# Audio.net
KiCad netlist of a schematic drawn in Altium Designer
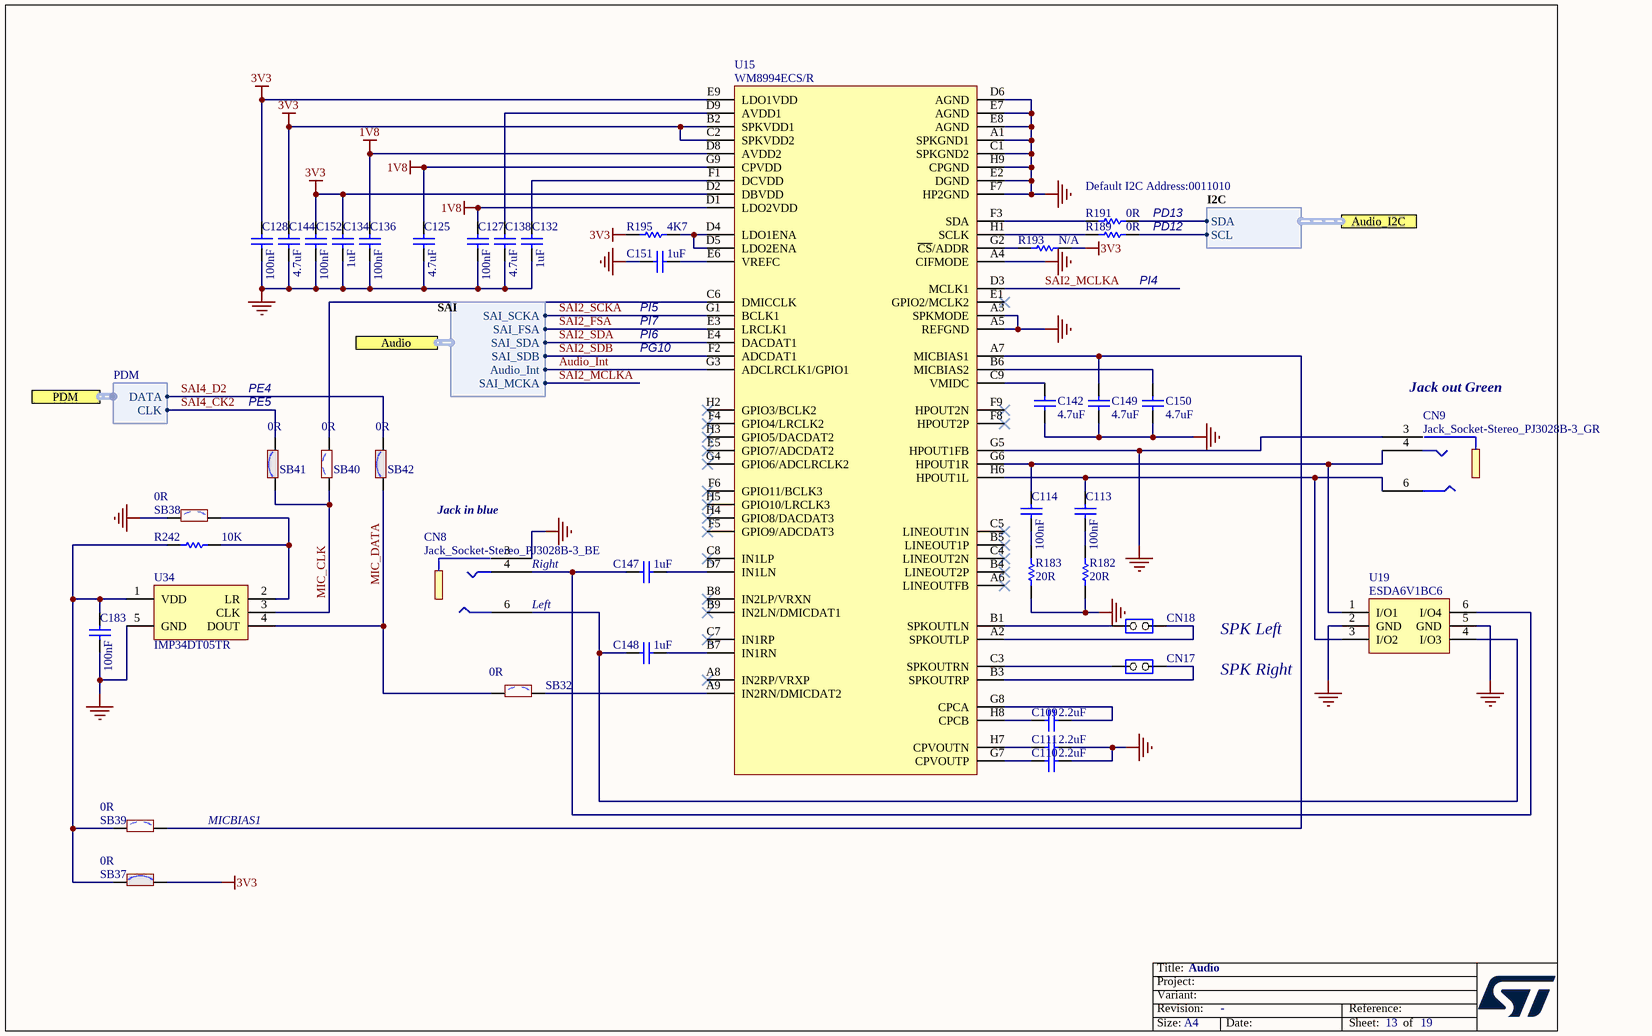
[diagram p0: Audio.SchDoc]

(export (version "E")
  (design (tool "Eeschema 10.0.6"))
  (components
    (comp (ref "C109")
      (value "2.2uF")
      (footprint "C0603")
      (description "Capacitor, MLCC, 2.2uF, 10V, X5R, 10%, 0603, T=0,8mm")
      (fields
        (field (name "INTERNAL_PART_NUMBER") "MCD-00012")
        (field (name "MANUFACTURER_PART_NUMBER") "CC0603KRX5R6BB225")
        (field (name "PROVIDED_BY") "Subcon")
      )
      (libsource (lib "MCD_PARTS_database") (part "Capacitor"))
    )
    (comp (ref "C110")
      (value "2.2uF")
      (footprint "C0603")
      (description "Capacitor, MLCC, 2.2uF, 10V, X5R, 10%, 0603, T=0,8mm")
      (fields
        (field (name "INTERNAL_PART_NUMBER") "MCD-00012")
        (field (name "MANUFACTURER_PART_NUMBER") "CC0603KRX5R6BB225")
        (field (name "PROVIDED_BY") "Subcon")
      )
      (libsource (lib "MCD_PARTS_database") (part "Capacitor"))
    )
    (comp (ref "C111")
      (value "2.2uF")
      (footprint "C0603")
      (description "Capacitor, MLCC, 2.2uF, 10V, X5R, 10%, 0603, T=0,8mm")
      (fields
        (field (name "INTERNAL_PART_NUMBER") "MCD-00012")
        (field (name "MANUFACTURER_PART_NUMBER") "CC0603KRX5R6BB225")
        (field (name "PROVIDED_BY") "Subcon")
      )
      (libsource (lib "MCD_PARTS_database") (part "Capacitor"))
    )
    (comp (ref "C113")
      (value "100nF")
      (footprint "C0402")
      (description "Capacitor, MLCC, 100nF, 16V, X7R, +/-10%, 0402, T=0.5mm")
      (fields
        (field (name "INTERNAL_PART_NUMBER") "MCD-00006")
        (field (name "MANUFACTURER_PART_NUMBER") "CC0402KRX7R7BB104")
      )
      (libsource (lib "MCD_PARTS_database") (part "Capacitor"))
    )
    (comp (ref "C114")
      (value "100nF")
      (footprint "C0402")
      (description "Capacitor, MLCC, 100nF, 16V, X7R, +/-10%, 0402, T=0.5mm")
      (fields
        (field (name "INTERNAL_PART_NUMBER") "MCD-00006")
        (field (name "MANUFACTURER_PART_NUMBER") "CC0402KRX7R7BB104")
      )
      (libsource (lib "MCD_PARTS_database") (part "Capacitor"))
    )
    (comp (ref "C125")
      (value "4.7uF")
      (footprint "C0603")
      (description "Capacitor, MLCC, 4.7uF, 16V, X5R, 10%, 0603, T=0.8mm")
      (fields
        (field (name "INTERNAL_PART_NUMBER") "MCD-00009")
        (field (name "MANUFACTURER_PART_NUMBER") "CC0603KRX5R7BB475")
        (field (name "PROVIDED_BY") "subcon")
      )
      (libsource (lib "MCD_PARTS_database") (part "Capacitor"))
    )
    (comp (ref "C127")
      (value "100nF")
      (footprint "C0402")
      (description "Capacitor, MLCC, 100nF, 16V, X7R, +/-10%, 0402, T=0.5mm")
      (fields
        (field (name "INTERNAL_PART_NUMBER") "MCD-00006")
        (field (name "MANUFACTURER_PART_NUMBER") "CC0402KRX7R7BB104")
      )
      (libsource (lib "MCD_PARTS_database") (part "Capacitor"))
    )
    (comp (ref "C128")
      (value "100nF")
      (footprint "C0402")
      (description "Capacitor, MLCC, 100nF, 16V, X7R, +/-10%, 0402, T=0.5mm")
      (fields
        (field (name "INTERNAL_PART_NUMBER") "MCD-00006")
        (field (name "MANUFACTURER_PART_NUMBER") "CC0402KRX7R7BB104")
      )
      (libsource (lib "MCD_PARTS_database") (part "Capacitor"))
    )
    (comp (ref "C132")
      (value "1uF")
      (footprint "C0603")
      (description "Capacitor, MLCC, 1uF, 16V, X5R, 10%, 0603, T=0,8mm")
      (fields
        (field (name "INTERNAL_PART_NUMBER") "MCD-00010")
        (field (name "MANUFACTURER_PART_NUMBER") "CC0603KRX5R7BB105")
        (field (name "PROVIDED_BY") "Subcon")
      )
      (libsource (lib "MCD_PARTS_database") (part "Capacitor"))
    )
    (comp (ref "C134")
      (value "1uF")
      (footprint "C0603")
      (description "Capacitor, MLCC, 1uF, 16V, X5R, 10%, 0603, T=0,8mm")
      (fields
        (field (name "INTERNAL_PART_NUMBER") "MCD-00010")
        (field (name "MANUFACTURER_PART_NUMBER") "CC0603KRX5R7BB105")
        (field (name "PROVIDED_BY") "Subcon")
      )
      (libsource (lib "MCD_PARTS_database") (part "Capacitor"))
    )
    (comp (ref "C136")
      (value "100nF")
      (footprint "C0402")
      (description "Capacitor, MLCC, 100nF, 16V, X7R, +/-10%, 0402, T=0.5mm")
      (fields
        (field (name "INTERNAL_PART_NUMBER") "MCD-00006")
        (field (name "MANUFACTURER_PART_NUMBER") "CC0402KRX7R7BB104")
      )
      (libsource (lib "MCD_PARTS_database") (part "Capacitor"))
    )
    (comp (ref "C138")
      (value "4.7uF")
      (footprint "C0603")
      (description "Capacitor, MLCC, 4.7uF, 16V, X5R, 10%, 0603, T=0.8mm")
      (fields
        (field (name "INTERNAL_PART_NUMBER") "MCD-00009")
        (field (name "MANUFACTURER_PART_NUMBER") "CC0603KRX5R7BB475")
        (field (name "PROVIDED_BY") "subcon")
      )
      (libsource (lib "MCD_PARTS_database") (part "Capacitor"))
    )
    (comp (ref "C142")
      (value "4.7uF")
      (footprint "C0603")
      (description "Capacitor, MLCC, 4.7uF, 16V, X5R, 10%, 0603, T=0.8mm")
      (fields
        (field (name "INTERNAL_PART_NUMBER") "MCD-00009")
        (field (name "MANUFACTURER_PART_NUMBER") "CC0603KRX5R7BB475")
        (field (name "PROVIDED_BY") "subcon")
      )
      (libsource (lib "MCD_PARTS_database") (part "Capacitor"))
    )
    (comp (ref "C144")
      (value "4.7uF")
      (footprint "C0603")
      (description "Capacitor, MLCC, 4.7uF, 16V, X5R, 10%, 0603, T=0.8mm")
      (fields
        (field (name "INTERNAL_PART_NUMBER") "MCD-00009")
        (field (name "MANUFACTURER_PART_NUMBER") "CC0603KRX5R7BB475")
        (field (name "PROVIDED_BY") "subcon")
      )
      (libsource (lib "MCD_PARTS_database") (part "Capacitor"))
    )
    (comp (ref "C147")
      (value "1uF")
      (footprint "C0603")
      (description "Capacitor, MLCC, 1uF, 16V, X5R, 10%, 0603, T=0,8mm")
      (fields
        (field (name "INTERNAL_PART_NUMBER") "MCD-00010")
        (field (name "MANUFACTURER_PART_NUMBER") "CC0603KRX5R7BB105")
        (field (name "PROVIDED_BY") "Subcon")
      )
      (libsource (lib "MCD_PARTS_database") (part "Capacitor"))
    )
    (comp (ref "C148")
      (value "1uF")
      (footprint "C0603")
      (description "Capacitor, MLCC, 1uF, 16V, X5R, 10%, 0603, T=0,8mm")
      (fields
        (field (name "INTERNAL_PART_NUMBER") "MCD-00010")
        (field (name "MANUFACTURER_PART_NUMBER") "CC0603KRX5R7BB105")
        (field (name "PROVIDED_BY") "Subcon")
      )
      (libsource (lib "MCD_PARTS_database") (part "Capacitor"))
    )
    (comp (ref "C149")
      (value "4.7uF")
      (footprint "C0603")
      (description "Capacitor, MLCC, 4.7uF, 16V, X5R, 10%, 0603, T=0.8mm")
      (fields
        (field (name "INTERNAL_PART_NUMBER") "MCD-00009")
        (field (name "MANUFACTURER_PART_NUMBER") "CC0603KRX5R7BB475")
        (field (name "PROVIDED_BY") "subcon")
      )
      (libsource (lib "MCD_PARTS_database") (part "Capacitor"))
    )
    (comp (ref "C150")
      (value "4.7uF")
      (footprint "C0603")
      (description "Capacitor, MLCC, 4.7uF, 16V, X5R, 10%, 0603, T=0.8mm")
      (fields
        (field (name "INTERNAL_PART_NUMBER") "MCD-00009")
        (field (name "MANUFACTURER_PART_NUMBER") "CC0603KRX5R7BB475")
        (field (name "PROVIDED_BY") "subcon")
      )
      (libsource (lib "MCD_PARTS_database") (part "Capacitor"))
    )
    (comp (ref "C151")
      (value "1uF")
      (footprint "C0603")
      (description "Capacitor, MLCC, 1uF, 16V, X5R, 10%, 0603, T=0,8mm")
      (fields
        (field (name "INTERNAL_PART_NUMBER") "MCD-00010")
        (field (name "MANUFACTURER_PART_NUMBER") "CC0603KRX5R7BB105")
        (field (name "PROVIDED_BY") "Subcon")
      )
      (libsource (lib "MCD_PARTS_database") (part "Capacitor"))
    )
    (comp (ref "C152")
      (value "100nF")
      (footprint "C0402")
      (description "Capacitor, MLCC, 100nF, 16V, X7R, +/-10%, 0402, T=0.5mm")
      (fields
        (field (name "INTERNAL_PART_NUMBER") "MCD-00006")
        (field (name "MANUFACTURER_PART_NUMBER") "CC0402KRX7R7BB104")
      )
      (libsource (lib "MCD_PARTS_database") (part "Capacitor"))
    )
    (comp (ref "C183")
      (value "100nF")
      (footprint "C0402")
      (description "Capacitor, MLCC, 100nF, 16V, X7R, +/-10%, 0402, T=0.5mm")
      (fields
        (field (name "INTERNAL_PART_NUMBER") "MCD-00006")
        (field (name "MANUFACTURER_PART_NUMBER") "CC0402KRX7R7BB104")
      )
      (libsource (lib "MCD_PARTS_database") (part "Capacitor"))
    )
    (comp (ref "CN8")
      (value "Jack_Socket-Stereo_PJ3028B-3_BE")
      (footprint "CON_PHONE-JACK-3P5_HY_PJ3028B")
      (description "Connector Jack socket Stereo 3.5mm, 3 pins, RA, SMT, Blue (Line input)")
      (fields
        (field (name "INTERNAL_PART_NUMBER") "MCD-00682")
        (field (name "MANUFACTURER_PART_NUMBER") "PJ3028B-3_BE")
        (field (name "PROVIDED_BY") "Subcon")
      )
      (libsource (lib "MCD_PARTS_database") (part "Jack_PJ3028B-3_3P"))
    )
    (comp (ref "CN9")
      (value "Jack_Socket-Stereo_PJ3028B-3_GR")
      (footprint "CON_PHONE-JACK-3P5_HY_PJ3028B")
      (description "Connector Jack socket Stereo 3.5mm, 3 pins, RA, SMT, Green (Line output)")
      (fields
        (field (name "INTERNAL_PART_NUMBER") "MCD-00018")
        (field (name "MANUFACTURER_PART_NUMBER") "PJ3028B-3_GR")
        (field (name "PROVIDED_BY") "Subcon")
      )
      (libsource (lib "") (part "Jack_PJ3028B-3_3P_1"))
    )
    (comp (ref "CN17")
      (value "Jumper Header 2x1")
      (footprint "CON_SAMTEC_TSW-102-07-G-S")
      (description "Header, 2x1, 2,54mm, VR, TH, Height 5.84mm/2.54mm")
      (fields
        (field (name "INTERNAL_PART_NUMBER") "MCD-00045")
        (field (name "MANUFACTURER_PART_NUMBER") "TSW-102-07-G-S")
        (field (name "PROVIDED_BY") "Subcon")
      )
      (libsource (lib "MCD_PARTS_database") (part "Jumper Header 2x1"))
    )
    (comp (ref "CN18")
      (value "Jumper Header 2x1")
      (footprint "CON_SAMTEC_TSW-102-07-G-S")
      (description "Header, 2x1, 2,54mm, VR, TH, Height 5.84mm/2.54mm")
      (fields
        (field (name "INTERNAL_PART_NUMBER") "MCD-00045")
        (field (name "MANUFACTURER_PART_NUMBER") "TSW-102-07-G-S")
        (field (name "PROVIDED_BY") "Subcon")
      )
      (libsource (lib "MCD_PARTS_database") (part "Jumper Header 2x1"))
    )
    (comp (ref "R182")
      (value "20R")
      (footprint "R0603")
      (description "Resistor,20R,0603,1%,1/10W")
      (fields
        (field (name "INTERNAL_PART_NUMBER") "MCD-00345")
        (field (name "MANUFACTURER_PART_NUMBER") "RC0603FR-0720RL")
        (field (name "PROVIDED_BY") "Subcon")
      )
      (libsource (lib "MCD_PARTS_database") (part "Resistor"))
    )
    (comp (ref "R183")
      (value "20R")
      (footprint "R0603")
      (description "Resistor,20R,0603,1%,1/10W")
      (fields
        (field (name "INTERNAL_PART_NUMBER") "MCD-00345")
        (field (name "MANUFACTURER_PART_NUMBER") "RC0603FR-0720RL")
        (field (name "PROVIDED_BY") "Subcon")
      )
      (libsource (lib "MCD_PARTS_database") (part "Resistor"))
    )
    (comp (ref "R189")
      (value "0R")
      (footprint "R0603")
      (description "Resistor,0R,0603,ULO")
      (fields
        (field (name "INTERNAL_PART_NUMBER") "MCD-00181")
        (field (name "MANUFACTURER_PART_NUMBER") "PMR03EZPJ000")
        (field (name "PROVIDED_BY") "Subcon")
      )
      (libsource (lib "MCD_PARTS_database") (part "Resistor"))
    )
    (comp (ref "R191")
      (value "0R")
      (footprint "R0603")
      (description "Resistor,0R,0603,ULO")
      (fields
        (field (name "INTERNAL_PART_NUMBER") "MCD-00181")
        (field (name "MANUFACTURER_PART_NUMBER") "PMR03EZPJ000")
        (field (name "PROVIDED_BY") "Subcon")
      )
      (libsource (lib "MCD_PARTS_database") (part "Resistor"))
    )
    (comp (ref "R193")
      (value "N/A")
      (footprint "R0402")
      (description "Resistor,10K,0402,1%,1/16W")
      (fields
        (field (name "INTERNAL_PART_NUMBER") "MCD-00053")
        (field (name "MANUFACTURER_PART_NUMBER") "RC0402FR-0710KL")
        (field (name "PROVIDED_BY") "subcon")
      )
      (libsource (lib "MCD_PARTS_database") (part "Resistor"))
    )
    (comp (ref "R195")
      (value "4K7")
      (footprint "R0603")
      (description "Resistor,4K7,0603,1%,1/10W")
      (fields
        (field (name "INTERNAL_PART_NUMBER") "MCD-00219")
        (field (name "MANUFACTURER_PART_NUMBER") "RC0603FR-074K7L")
        (field (name "PROVIDED_BY") "Subcon")
      )
      (libsource (lib "MCD_PARTS_database") (part "Resistor"))
    )
    (comp (ref "R242")
      (value "10K")
      (footprint "R0402")
      (description "Resistor,10K,0402,1%,1/16W")
      (fields
        (field (name "INTERNAL_PART_NUMBER") "MCD-00053")
        (field (name "MANUFACTURER_PART_NUMBER") "RC0402FR-0710KL")
        (field (name "PROVIDED_BY") "subcon")
      )
      (libsource (lib "MCD_PARTS_database") (part "Resistor"))
    )
    (comp (ref "SB32")
      (value "0R")
      (footprint "SOLDER-BRIDGE_R0603-0R")
      (description "Solder Bridge OFF")
      (fields (field (name "INTERNAL_PART_NUMBER") "MCD-00072") (field (name "MANUFACTURER") "YAGEO"))
      (libsource (lib "MCD_PARTS_database") (part "SB_OFF"))
    )
    (comp (ref "SB37")
      (value "0R")
      (footprint "SOLDER-BRIDGE_R0603-0R")
      (description "Solder Bridge ON")
      (fields
        (field (name "INTERNAL_PART_NUMBER") "MCD-00071")
        (field (name "MANUFACTURER") "YAGEO")
        (field (name "PROVIDED_BY") "Subcon")
      )
      (libsource (lib "") (part "SB_ON_1"))
    )
    (comp (ref "SB38")
      (value "0R")
      (footprint "SOLDER-BRIDGE_R0603-0R")
      (description "Solder Bridge OFF")
      (fields (field (name "INTERNAL_PART_NUMBER") "MCD-00072") (field (name "MANUFACTURER") "YAGEO"))
      (libsource (lib "MCD_PARTS_database") (part "SB_OFF"))
    )
    (comp (ref "SB39")
      (value "0R")
      (footprint "SOLDER-BRIDGE_R0603-0R")
      (description "Solder Bridge OFF")
      (fields (field (name "INTERNAL_PART_NUMBER") "MCD-00072") (field (name "MANUFACTURER") "YAGEO"))
      (libsource (lib "MCD_PARTS_database") (part "SB_OFF"))
    )
    (comp (ref "SB40")
      (value "0R")
      (footprint "SOLDER-BRIDGE_R0603-0R")
      (description "Solder Bridge OFF")
      (fields (field (name "INTERNAL_PART_NUMBER") "MCD-00072") (field (name "MANUFACTURER") "YAGEO"))
      (libsource (lib "") (part "SB_OFF_1"))
    )
    (comp (ref "SB41")
      (value "0R")
      (footprint "SOLDER-BRIDGE_R0603-0R")
      (description "Solder Bridge ON")
      (fields
        (field (name "INTERNAL_PART_NUMBER") "MCD-00071")
        (field (name "MANUFACTURER") "YAGEO")
        (field (name "PROVIDED_BY") "Subcon")
      )
      (libsource (lib "MCD_PARTS_database") (part "SB_ON"))
    )
    (comp (ref "SB42")
      (value "0R")
      (footprint "SOLDER-BRIDGE_R0603-0R")
      (description "Solder Bridge ON")
      (fields
        (field (name "INTERNAL_PART_NUMBER") "MCD-00071")
        (field (name "MANUFACTURER") "YAGEO")
        (field (name "PROVIDED_BY") "Subcon")
      )
      (libsource (lib "MCD_PARTS_database") (part "SB_ON"))
    )
    (comp (ref "U15")
      (value "WM8994ECS/R")
      (footprint "ICC_W-CSP-BGA72_4P511X4P023_P050")
      (description "Multi-Channel Audio Hub CODEC for Smartphones")
      (fields
        (field (name "INTERNAL_PART_NUMBER") "MCD-00079")
        (field (name "MANUFACTURER") "CIRRUS LOGIC")
        (field (name "PROVIDED_BY") "Subcon")
      )
      (libsource (lib "MCD_PARTS_database") (part "WM8994ECS/R"))
    )
    (comp (ref "U19")
      (value "ESDA6V1BC6")
      (footprint "ESD_SOT23-6L")
      (description "Quad Bidir ESD protection")
      (fields
        (field (name "INTERNAL_PART_NUMBER") "MCD-00247")
        (field (name "MANUFACTURER") "STMICROELECTRONICS")
        (field (name "PROVIDED_BY") "Subcon")
      )
      (libsource (lib "MCD_PARTS_database") (part "ESDA6V1BC6"))
    )
    (comp (ref "U34")
      (value "IMP34DT05TR")
      (footprint "MIC_HCLGA_3X4X1_4LD")
      (description "MEMS audio sensor omnidirectional digital microphone for industrial applications")
      (fields (field (name "INTERNAL_PART_NUMBER") "MCD-01715") (field (name "BMS_PART_NUMBER") "9177995"))
      (libsource (lib "MCD_PARTS_database") (part "IMP34DT05TR"))
    )
  )
  (nets
    (net (code "4") (name "/Audio_Int") (class "Default")
      (node (ref "U15") (pin "G3") (pinfunction "ADCLRCLK1/GPIO1_G3") (pintype "passive"))
    )
    (net (code "5") (name "/MIC_CLK") (class "Default")
      (node (ref "SB40") (pin "1") (pinfunction "1_1") (pintype "passive"))
      (node (ref "SB41") (pin "1") (pinfunction "1_1") (pintype "passive"))
      (node (ref "U34") (pin "3") (pinfunction "CLK_3") (pintype "passive"))
    )
    (net (code "6") (name "/MIC_DATA") (class "Default")
      (node (ref "SB32") (pin "1") (pinfunction "1_1") (pintype "passive"))
      (node (ref "SB42") (pin "1") (pinfunction "1_1") (pintype "passive"))
      (node (ref "U34") (pin "4") (pinfunction "DOUT_4") (pintype "passive"))
    )
    (net (code "7") (name "/SAI2_FSA") (class "Default")
      (node (ref "U15") (pin "E3") (pinfunction "LRCLK1_E3") (pintype "passive"))
    )
    (net (code "8") (name "/SAI2_MCLKA") (class "Default")
      (node (ref "U15") (pin "D3") (pinfunction "MCLK1_D3") (pintype "passive"))
    )
    (net (code "9") (name "/SAI2_SCKA") (class "Default")
      (node (ref "U15") (pin "G1") (pinfunction "BCLK1_G1") (pintype "passive"))
    )
    (net (code "10") (name "/SAI2_SDA") (class "Default")
      (node (ref "U15") (pin "E4") (pinfunction "DACDAT1_E4") (pintype "passive"))
    )
    (net (code "11") (name "/SAI2_SDB") (class "Default")
      (node (ref "U15") (pin "F2") (pinfunction "ADCDAT1_F2") (pintype "passive"))
    )
    (net (code "12") (name "/SAI4_CK2") (class "Default")
      (node (ref "SB41") (pin "2") (pinfunction "2_2") (pintype "passive"))
    )
    (net (code "13") (name "/SAI4_D2") (class "Default")
      (node (ref "SB42") (pin "2") (pinfunction "2_2") (pintype "passive"))
    )
    (net (code "14") (name "/SCL") (class "Default")
      (node (ref "R189") (pin "2") (pinfunction "2_2") (pintype "passive"))
    )
    (net (code "15") (name "/SDA") (class "Default")
      (node (ref "R191") (pin "2") (pinfunction "2_2") (pintype "passive"))
    )
    (net (code "19") (name "1V8") (class "Default")
      (node (ref "C125") (pin "2") (pinfunction "2_2") (pintype "passive"))
      (node (ref "C127") (pin "1") (pinfunction "1_1") (pintype "passive"))
      (node (ref "C136") (pin "1") (pinfunction "1_1") (pintype "passive"))
      (node (ref "U15") (pin "D1") (pinfunction "LDO2VDD_D1") (pintype "passive"))
      (node (ref "U15") (pin "D8") (pinfunction "AVDD2_D8") (pintype "passive"))
      (node (ref "U15") (pin "G9") (pinfunction "CPVDD_G9") (pintype "passive"))
    )
    (net (code "20") (name "3V3") (class "Default")
      (node (ref "C128") (pin "1") (pinfunction "1_1") (pintype "passive"))
      (node (ref "C134") (pin "2") (pinfunction "2_2") (pintype "passive"))
      (node (ref "C144") (pin "2") (pinfunction "2_2") (pintype "passive"))
      (node (ref "C152") (pin "1") (pinfunction "1_1") (pintype "passive"))
      (node (ref "R193") (pin "1") (pinfunction "1_1") (pintype "passive"))
      (node (ref "R195") (pin "1") (pinfunction "1_1") (pintype "passive"))
      (node (ref "SB37") (pin "2") (pinfunction "2_2") (pintype "passive"))
      (node (ref "U15") (pin "B2") (pinfunction "SPKVDD1_B2") (pintype "passive"))
      (node (ref "U15") (pin "C2") (pinfunction "SPKVDD2_C2") (pintype "passive"))
      (node (ref "U15") (pin "D2") (pinfunction "DBVDD_D2") (pintype "passive"))
      (node (ref "U15") (pin "E9") (pinfunction "LDO1VDD_E9") (pintype "passive"))
    )
    (net (code "21") (name "GND") (class "Default")
      (node (ref "C110") (pin "1") (pinfunction "1_1") (pintype "passive"))
      (node (ref "C111") (pin "1") (pinfunction "1_1") (pintype "passive"))
      (node (ref "C125") (pin "1") (pinfunction "1_1") (pintype "passive"))
      (node (ref "C127") (pin "2") (pinfunction "2_2") (pintype "passive"))
      (node (ref "C128") (pin "2") (pinfunction "2_2") (pintype "passive"))
      (node (ref "C132") (pin "1") (pinfunction "1_1") (pintype "passive"))
      (node (ref "C134") (pin "1") (pinfunction "1_1") (pintype "passive"))
      (node (ref "C136") (pin "2") (pinfunction "2_2") (pintype "passive"))
      (node (ref "C138") (pin "1") (pinfunction "1_1") (pintype "passive"))
      (node (ref "C142") (pin "1") (pinfunction "1_1") (pintype "passive"))
      (node (ref "C144") (pin "1") (pinfunction "1_1") (pintype "passive"))
      (node (ref "C149") (pin "1") (pinfunction "1_1") (pintype "passive"))
      (node (ref "C150") (pin "1") (pinfunction "1_1") (pintype "passive"))
      (node (ref "C151") (pin "2") (pinfunction "2_2") (pintype "passive"))
      (node (ref "C152") (pin "2") (pinfunction "2_2") (pintype "passive"))
      (node (ref "C183") (pin "2") (pinfunction "2_2") (pintype "passive"))
      (node (ref "CN8") (pin "3") (pintype "passive"))
      (node (ref "CN9") (pin "3") (pintype "passive"))
      (node (ref "R182") (pin "1") (pinfunction "1_1") (pintype "passive"))
      (node (ref "R183") (pin "1") (pinfunction "1_1") (pintype "passive"))
      (node (ref "SB38") (pin "1") (pinfunction "1_1") (pintype "passive"))
      (node (ref "U15") (pin "A1") (pinfunction "SPKGND1_A1") (pintype "passive"))
      (node (ref "U15") (pin "A3") (pinfunction "SPKMODE_A3") (pintype "passive"))
      (node (ref "U15") (pin "A4") (pinfunction "CIFMODE_A4") (pintype "passive"))
      (node (ref "U15") (pin "A5") (pinfunction "REFGND_A5") (pintype "passive"))
      (node (ref "U15") (pin "C1") (pinfunction "SPKGND2_C1") (pintype "passive"))
      (node (ref "U15") (pin "D6") (pinfunction "AGND_D6") (pintype "passive"))
      (node (ref "U15") (pin "E2") (pinfunction "DGND_E2") (pintype "passive"))
      (node (ref "U15") (pin "E7") (pinfunction "AGND_E7") (pintype "passive"))
      (node (ref "U15") (pin "E8") (pinfunction "AGND_E8") (pintype "passive"))
      (node (ref "U15") (pin "F7") (pinfunction "HP2GND_F7") (pintype "passive"))
      (node (ref "U15") (pin "G5") (pinfunction "HPOUT1FB_G5") (pintype "passive"))
      (node (ref "U15") (pin "H9") (pinfunction "CPGND_H9") (pintype "passive"))
      (node (ref "U19") (pin "2") (pinfunction "GND_2") (pintype "passive"))
      (node (ref "U19") (pin "5") (pinfunction "GND_5") (pintype "passive"))
      (node (ref "U34") (pin "5") (pinfunction "GND_5") (pintype "passive"))
    )
    (net (code "22") (name "Net-(C113-Pad2)") (class "Default")
      (node (ref "C113") (pin "2") (pinfunction "2_2") (pintype "passive"))
      (node (ref "R182") (pin "2") (pinfunction "2_2") (pintype "passive"))
    )
    (net (code "23") (name "Net-(C114-Pad2)") (class "Default")
      (node (ref "C114") (pin "2") (pinfunction "2_2") (pintype "passive"))
      (node (ref "R183") (pin "2") (pinfunction "2_2") (pintype "passive"))
    )
    (net (code "24") (name "Net-(CN17-COMMON)") (class "Default")
      (node (ref "CN17") (pin "1") (pinfunction "COMMON_1") (pintype "passive"))
      (node (ref "U15") (pin "B3") (pinfunction "SPKOUTRP_B3") (pintype "passive"))
    )
    (net (code "25") (name "Net-(CN17-NO)") (class "Default")
      (node (ref "CN17") (pin "2") (pinfunction "NO_2") (pintype "passive"))
      (node (ref "U15") (pin "C3") (pinfunction "SPKOUTRN_C3") (pintype "passive"))
    )
    (net (code "26") (name "Net-(CN18-COMMON)") (class "Default")
      (node (ref "CN18") (pin "1") (pinfunction "COMMON_1") (pintype "passive"))
      (node (ref "U15") (pin "A2") (pinfunction "SPKOUTLP_A2") (pintype "passive"))
    )
    (net (code "27") (name "Net-(CN18-NO)") (class "Default")
      (node (ref "CN18") (pin "2") (pinfunction "NO_2") (pintype "passive"))
      (node (ref "U15") (pin "B1") (pinfunction "SPKOUTLN_B1") (pintype "passive"))
    )
    (net (code "28") (name "Net-(U15-AVDD1)") (class "Default")
      (node (ref "C138") (pin "2") (pinfunction "2_2") (pintype "passive"))
      (node (ref "U15") (pin "D9") (pinfunction "AVDD1_D9") (pintype "passive"))
    )
    (net (code "29") (name "Net-(U15-CPCA)") (class "Default")
      (node (ref "C109") (pin "1") (pinfunction "1_1") (pintype "passive"))
      (node (ref "U15") (pin "G8") (pinfunction "CPCA_G8") (pintype "passive"))
    )
    (net (code "30") (name "Net-(U15-CPCB)") (class "Default")
      (node (ref "C109") (pin "2") (pinfunction "2_2") (pintype "passive"))
      (node (ref "U15") (pin "H8") (pinfunction "CPCB_H8") (pintype "passive"))
    )
    (net (code "31") (name "Net-(U15-CPVOUTN)") (class "Default")
      (node (ref "C111") (pin "2") (pinfunction "2_2") (pintype "passive"))
      (node (ref "U15") (pin "H7") (pinfunction "CPVOUTN_H7") (pintype "passive"))
    )
    (net (code "32") (name "Net-(U15-CPVOUTP)") (class "Default")
      (node (ref "C110") (pin "2") (pinfunction "2_2") (pintype "passive"))
      (node (ref "U15") (pin "G7") (pinfunction "CPVOUTP_G7") (pintype "passive"))
    )
    (net (code "33") (name "Net-(U15-DCVDD)") (class "Default")
      (node (ref "C132") (pin "2") (pinfunction "2_2") (pintype "passive"))
      (node (ref "U15") (pin "F1") (pinfunction "DCVDD_F1") (pintype "passive"))
    )
    (net (code "34") (name "Net-(U15-DMICCLK)") (class "Default")
      (node (ref "SB40") (pin "2") (pinfunction "2_2") (pintype "passive"))
      (node (ref "U15") (pin "C6") (pinfunction "DMICCLK_C6") (pintype "passive"))
    )
    (net (code "35") (name "Net-(U15-HPOUT1L)") (class "Default")
      (node (ref "C113") (pin "1") (pinfunction "1_1") (pintype "passive"))
      (node (ref "CN9") (pin "6") (pintype "passive"))
      (node (ref "U15") (pin "H6") (pinfunction "HPOUT1L_H6") (pintype "passive"))
      (node (ref "U19") (pin "3") (pinfunction "I/O2_3") (pintype "passive"))
    )
    (net (code "36") (name "Net-(U15-HPOUT1R)") (class "Default")
      (node (ref "C114") (pin "1") (pinfunction "1_1") (pintype "passive"))
      (node (ref "CN9") (pin "4") (pintype "passive"))
      (node (ref "U15") (pin "G6") (pinfunction "HPOUT1R_G6") (pintype "passive"))
      (node (ref "U19") (pin "1") (pinfunction "I/O1_1") (pintype "passive"))
    )
    (net (code "37") (name "Net-(U15-IN1LN)") (class "Default")
      (node (ref "C147") (pin "1") (pinfunction "1_1") (pintype "passive"))
      (node (ref "U15") (pin "D7") (pinfunction "IN1LN_D7") (pintype "passive"))
    )
    (net (code "38") (name "Net-(U15-IN1RN)") (class "Default")
      (node (ref "C148") (pin "1") (pinfunction "1_1") (pintype "passive"))
      (node (ref "U15") (pin "B7") (pinfunction "IN1RN_B7") (pintype "passive"))
    )
    (net (code "39") (name "Net-(U15-IN2RN{slash}DMICDAT2)") (class "Default")
      (node (ref "SB32") (pin "2") (pinfunction "2_2") (pintype "passive"))
      (node (ref "U15") (pin "A9") (pinfunction "IN2RN/DMICDAT2_A9") (pintype "passive"))
    )
    (net (code "40") (name "Net-(U15-LDO1ENA)") (class "Default")
      (node (ref "R195") (pin "2") (pinfunction "2_2") (pintype "passive"))
      (node (ref "U15") (pin "D4") (pinfunction "LDO1ENA_D4") (pintype "passive"))
      (node (ref "U15") (pin "D5") (pinfunction "LDO2ENA_D5") (pintype "passive"))
    )
    (net (code "41") (name "Net-(U15-MICBIAS1)") (class "Default")
      (node (ref "C149") (pin "2") (pinfunction "2_2") (pintype "passive"))
      (node (ref "SB39") (pin "2") (pinfunction "2_2") (pintype "passive"))
      (node (ref "U15") (pin "A7") (pinfunction "MICBIAS1_A7") (pintype "passive"))
    )
    (net (code "42") (name "Net-(U15-MICBIAS2)") (class "Default")
      (node (ref "C150") (pin "2") (pinfunction "2_2") (pintype "passive"))
      (node (ref "U15") (pin "B6") (pinfunction "MICBIAS2_B6") (pintype "passive"))
    )
    (net (code "43") (name "Net-(U15-SCLK)") (class "Default")
      (node (ref "R189") (pin "1") (pinfunction "1_1") (pintype "passive"))
      (node (ref "U15") (pin "H1") (pinfunction "SCLK_H1") (pintype "passive"))
    )
    (net (code "44") (name "Net-(U15-SDA)") (class "Default")
      (node (ref "R191") (pin "1") (pinfunction "1_1") (pintype "passive"))
      (node (ref "U15") (pin "F3") (pinfunction "SDA_F3") (pintype "passive"))
    )
    (net (code "45") (name "Net-(U15-VMIDC)") (class "Default")
      (node (ref "C142") (pin "2") (pinfunction "2_2") (pintype "passive"))
      (node (ref "U15") (pin "C9") (pinfunction "VMIDC_C9") (pintype "passive"))
    )
    (net (code "46") (name "Net-(U15-VREFC)") (class "Default")
      (node (ref "C151") (pin "1") (pinfunction "1_1") (pintype "passive"))
      (node (ref "U15") (pin "E6") (pinfunction "VREFC_E6") (pintype "passive"))
    )
    (net (code "47") (name "Net-(U15-~{CS}{slash}ADDR)") (class "Default")
      (node (ref "R193") (pin "2") (pinfunction "2_2") (pintype "passive"))
      (node (ref "U15") (pin "G2") (pinfunction "~{CS}/ADDR_G2") (pintype "passive"))
    )
    (net (code "48") (name "Net-(U19-I{slash}O3)") (class "Default")
      (node (ref "C148") (pin "2") (pinfunction "2_2") (pintype "passive"))
      (node (ref "CN8") (pin "6") (pintype "passive"))
      (node (ref "U19") (pin "4") (pinfunction "I/O3_4") (pintype "passive"))
    )
    (net (code "49") (name "Net-(U19-I{slash}O4)") (class "Default")
      (node (ref "C147") (pin "2") (pinfunction "2_2") (pintype "passive"))
      (node (ref "CN8") (pin "4") (pintype "passive"))
      (node (ref "U19") (pin "6") (pinfunction "I/O4_6") (pintype "passive"))
    )
    (net (code "50") (name "Net-(U34-LR)") (class "Default")
      (node (ref "R242") (pin "1") (pinfunction "1_1") (pintype "passive"))
      (node (ref "SB38") (pin "2") (pinfunction "2_2") (pintype "passive"))
      (node (ref "U34") (pin "2") (pinfunction "LR_2") (pintype "passive"))
    )
    (net (code "51") (name "Net-(U34-VDD)") (class "Default")
      (node (ref "C183") (pin "1") (pinfunction "1_1") (pintype "passive"))
      (node (ref "R242") (pin "2") (pinfunction "2_2") (pintype "passive"))
      (node (ref "SB37") (pin "1") (pinfunction "1_1") (pintype "passive"))
      (node (ref "SB39") (pin "1") (pinfunction "1_1") (pintype "passive"))
      (node (ref "U34") (pin "1") (pinfunction "VDD_1") (pintype "passive"))
    )
    (net (code "52") (name "unconnected-(U15-GPIO2{slash}MCLK2-PadE1)") (class "Default")
      (node (ref "U15") (pin "E1") (pinfunction "GPIO2/MCLK2_E1") (pintype "passive+no_connect"))
    )
    (net (code "53") (name "unconnected-(U15-GPIO3{slash}BCLK2-PadH2)") (class "Default")
      (node (ref "U15") (pin "H2") (pinfunction "GPIO3/BCLK2_H2") (pintype "passive+no_connect"))
    )
    (net (code "54") (name "unconnected-(U15-GPIO4{slash}LRCLK2-PadF4)") (class "Default")
      (node (ref "U15") (pin "F4") (pinfunction "GPIO4/LRCLK2_F4") (pintype "passive+no_connect"))
    )
    (net (code "55") (name "unconnected-(U15-GPIO5{slash}DACDAT2-PadH3)") (class "Default")
      (node (ref "U15") (pin "H3") (pinfunction "GPIO5/DACDAT2_H3") (pintype "passive+no_connect"))
    )
    (net (code "56") (name "unconnected-(U15-GPIO6{slash}ADCLRCLK2-PadG4)") (class "Default")
      (node (ref "U15") (pin "G4") (pinfunction "GPIO6/ADCLRCLK2_G4") (pintype "passive+no_connect"))
    )
    (net (code "57") (name "unconnected-(U15-GPIO7{slash}ADCDAT2-PadE5)") (class "Default")
      (node (ref "U15") (pin "E5") (pinfunction "GPIO7/ADCDAT2_E5") (pintype "passive+no_connect"))
    )
    (net (code "58") (name "unconnected-(U15-GPIO8{slash}DACDAT3-PadH4)") (class "Default")
      (node (ref "U15") (pin "H4") (pinfunction "GPIO8/DACDAT3_H4") (pintype "passive+no_connect"))
    )
    (net (code "59") (name "unconnected-(U15-GPIO9{slash}ADCDAT3-PadF5)") (class "Default")
      (node (ref "U15") (pin "F5") (pinfunction "GPIO9/ADCDAT3_F5") (pintype "passive+no_connect"))
    )
    (net (code "60") (name "unconnected-(U15-GPIO10{slash}LRCLK3-PadH5)") (class "Default")
      (node (ref "U15") (pin "H5") (pinfunction "GPIO10/LRCLK3_H5") (pintype "passive+no_connect"))
    )
    (net (code "61") (name "unconnected-(U15-GPIO11{slash}BCLK3-PadF6)") (class "Default")
      (node (ref "U15") (pin "F6") (pinfunction "GPIO11/BCLK3_F6") (pintype "passive+no_connect"))
    )
    (net (code "62") (name "unconnected-(U15-HPOUT2N-PadF9)") (class "Default")
      (node (ref "U15") (pin "F9") (pinfunction "HPOUT2N_F9") (pintype "passive+no_connect"))
    )
    (net (code "63") (name "unconnected-(U15-HPOUT2P-PadF8)") (class "Default")
      (node (ref "U15") (pin "F8") (pinfunction "HPOUT2P_F8") (pintype "passive+no_connect"))
    )
    (net (code "64") (name "unconnected-(U15-IN1LP-PadC8)") (class "Default")
      (node (ref "U15") (pin "C8") (pinfunction "IN1LP_C8") (pintype "passive+no_connect"))
    )
    (net (code "65") (name "unconnected-(U15-IN1RP-PadC7)") (class "Default")
      (node (ref "U15") (pin "C7") (pinfunction "IN1RP_C7") (pintype "passive+no_connect"))
    )
    (net (code "66") (name "unconnected-(U15-IN2LN{slash}DMICDAT1-PadB9)") (class "Default")
      (node (ref "U15") (pin "B9") (pinfunction "IN2LN/DMICDAT1_B9") (pintype "passive+no_connect"))
    )
    (net (code "67") (name "unconnected-(U15-IN2LP{slash}VRXN-PadB8)") (class "Default")
      (node (ref "U15") (pin "B8") (pinfunction "IN2LP/VRXN_B8") (pintype "passive+no_connect"))
    )
    (net (code "68") (name "unconnected-(U15-IN2RP{slash}VRXP-PadA8)") (class "Default")
      (node (ref "U15") (pin "A8") (pinfunction "IN2RP/VRXP_A8") (pintype "passive+no_connect"))
    )
    (net (code "69") (name "unconnected-(U15-LINEOUT1N-PadC5)") (class "Default")
      (node (ref "U15") (pin "C5") (pinfunction "LINEOUT1N_C5") (pintype "passive+no_connect"))
    )
    (net (code "70") (name "unconnected-(U15-LINEOUT1P-PadB5)") (class "Default")
      (node (ref "U15") (pin "B5") (pinfunction "LINEOUT1P_B5") (pintype "passive+no_connect"))
    )
    (net (code "71") (name "unconnected-(U15-LINEOUT2N-PadC4)") (class "Default")
      (node (ref "U15") (pin "C4") (pinfunction "LINEOUT2N_C4") (pintype "passive+no_connect"))
    )
    (net (code "72") (name "unconnected-(U15-LINEOUT2P-PadB4)") (class "Default")
      (node (ref "U15") (pin "B4") (pinfunction "LINEOUT2P_B4") (pintype "passive+no_connect"))
    )
    (net (code "73") (name "unconnected-(U15-LINEOUTFB-PadA6)") (class "Default")
      (node (ref "U15") (pin "A6") (pinfunction "LINEOUTFB_A6") (pintype "passive+no_connect"))
    )
  )
)
